# top_schema.net
KiCad netlist of a schematic drawn in Altium Designer
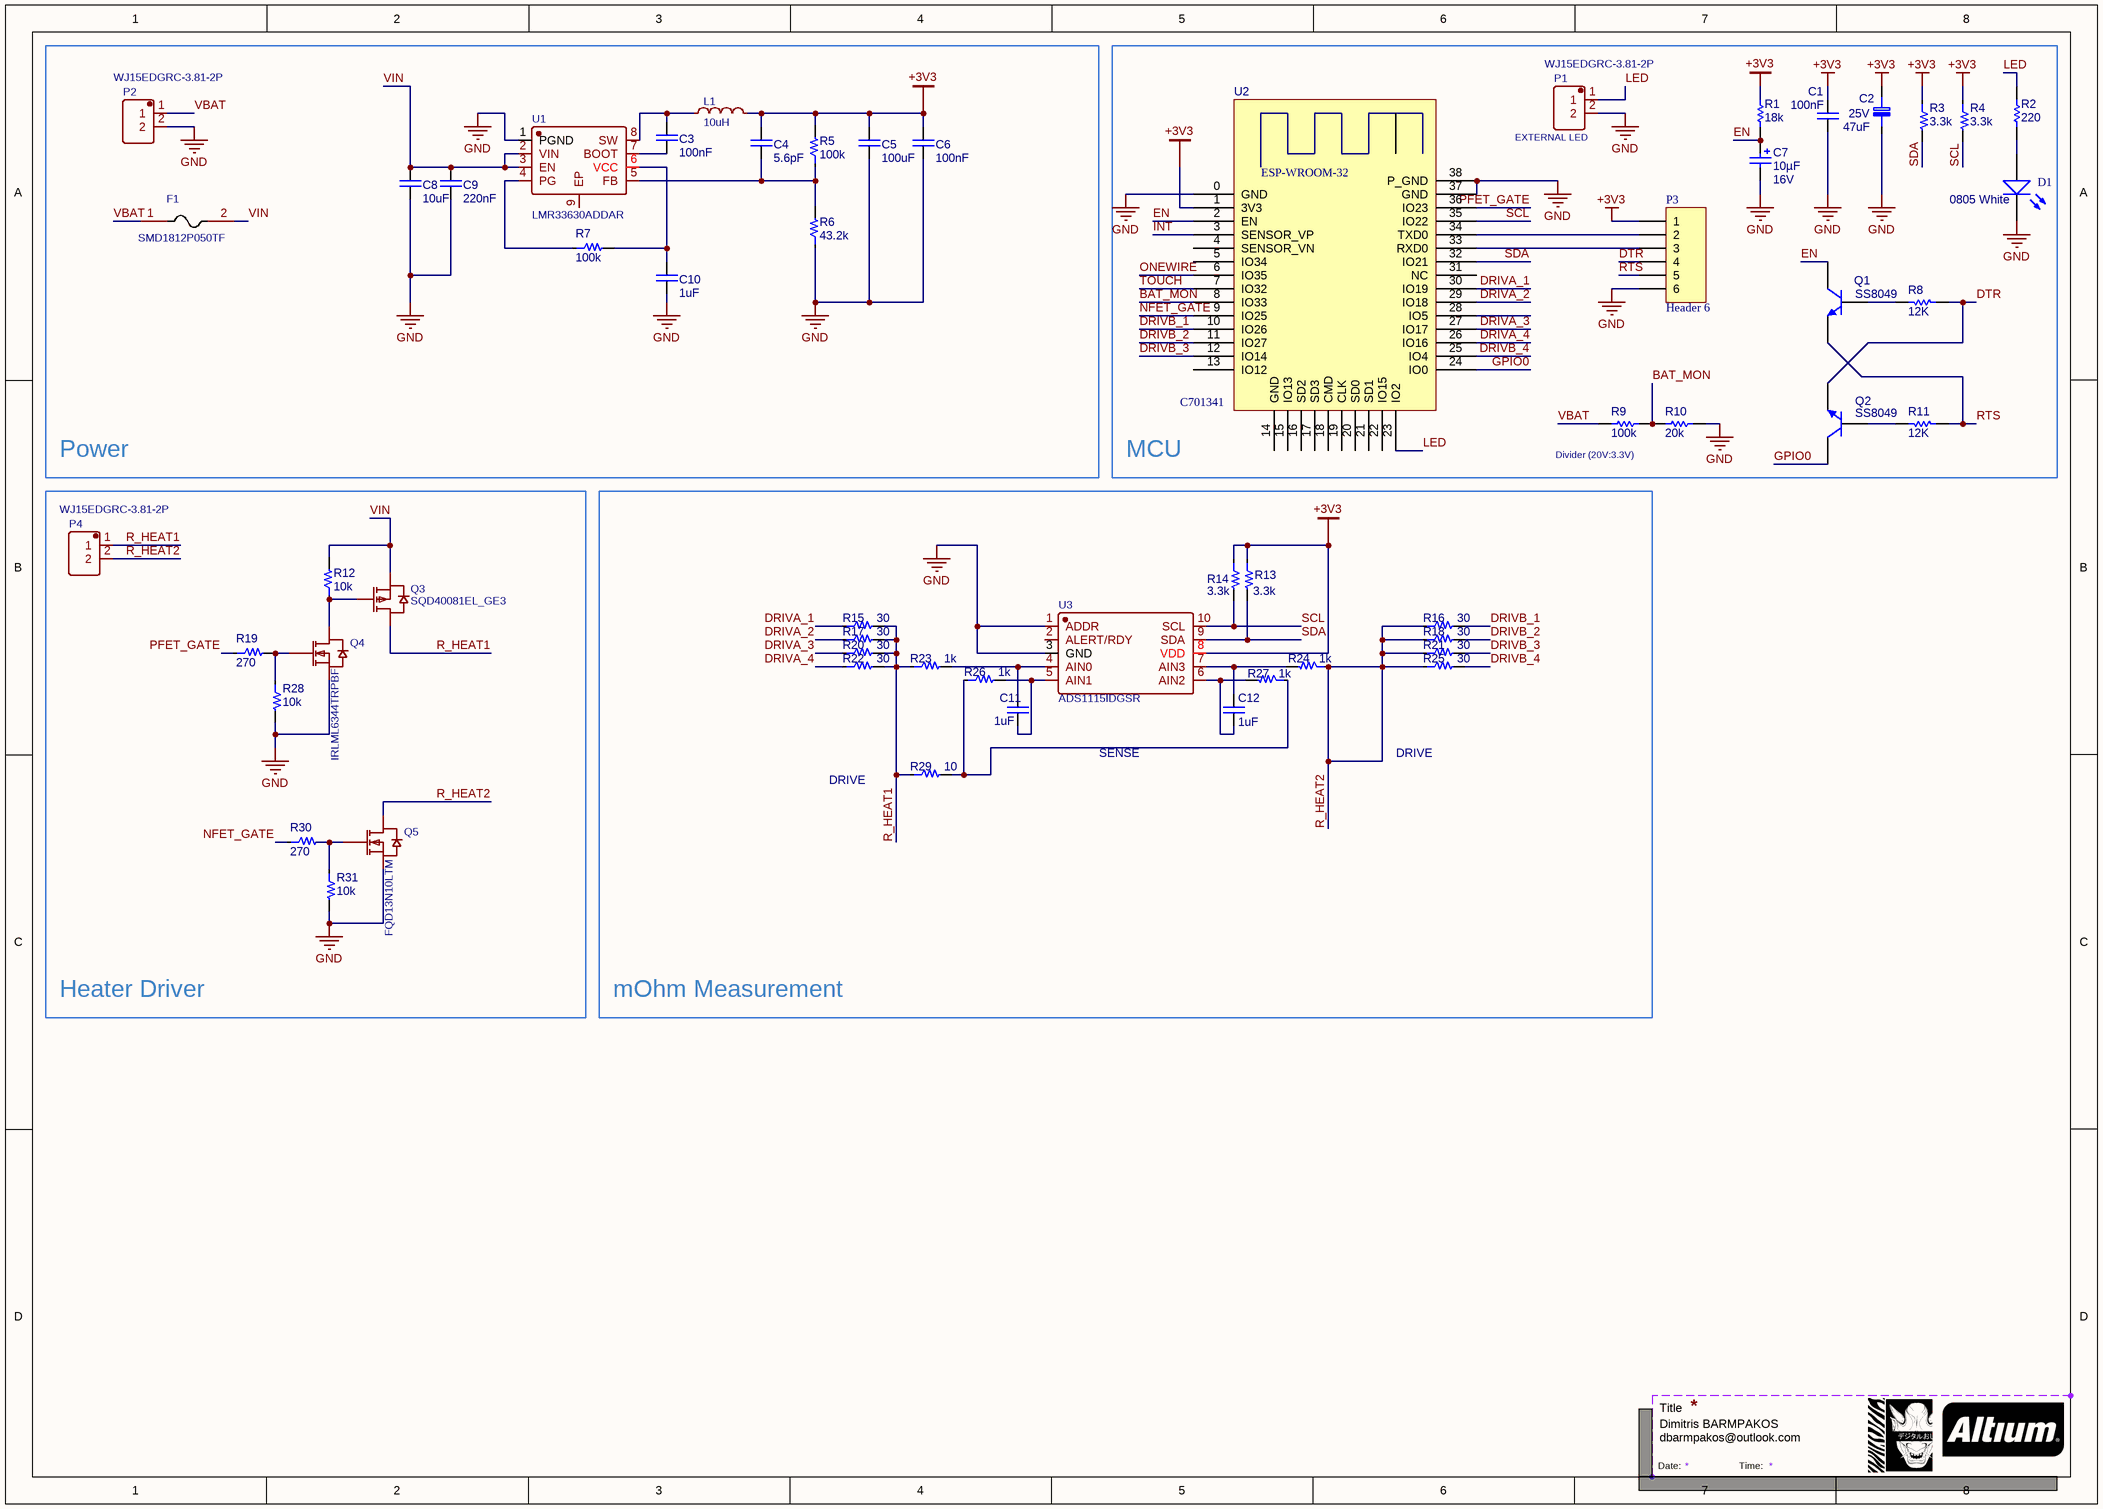
[diagram p0: top_schema.SchDoc]

(export (version "E")
  (design (tool "Eeschema 10.0.6"))
  (components
    (comp (ref "C1")
      (value "100nF")
      (footprint "CAP_0603")
      (description "CAP CER 0.1UF 50V X7R 0603")
      (fields
        (field (name "MANUFACTURER") "FH(Guangdong Fenghua Advanced Tech)")
        (field (name "MANUFACTURER PART NUMBER") "0603F104M500NT")
      )
      (libsource (lib "Schlib1") (part "CAP - CER 0.1UF 25V X7R 0805"))
    )
    (comp (ref "C2")
      (value "47uF")
      (footprint "CAP SMD 6.3X7.7")
      (description "CAP ALUM 22UF 20% 25V SMD")
      (fields
        (field (name "MANUFACTURER") "Nichicon")
        (field (name "MANUFACTURER PART NUMBER") "UWX1E220MCL1GB")
        (field (name "CAPACITANCE") "47uF")
        (field (name "VOLTAGE RATING") "25V")
      )
      (libsource (lib "Schlib1") (part "CAP 22UF 63V SMD"))
    )
    (comp (ref "C3")
      (value "100nF")
      (footprint "CAP_0603")
      (description "CAP CER 0.1UF 50V X7R 0603")
      (fields
        (field (name "MANUFACTURER") "FH(Guangdong Fenghua Advanced Tech)")
        (field (name "MANUFACTURER PART NUMBER") "0603F104M500NT")
      )
      (libsource (lib "thermoskin_v1") (part "CAP - CER 0.1UF 25V X7R 0805"))
    )
    (comp (ref "C4")
      (value "5.6pF")
      (footprint "CAP_0603")
      (description "CAP CER 0.1UF 50V X7R 0603")
      (fields
        (field (name "MANUFACTURER") "FH(Guangdong Fenghua Advanced Tech)")
        (field (name "MANUFACTURER PART NUMBER") "0603F104M500NT")
      )
      (libsource (lib "thermoskin_v1") (part "CAP - CER 0.1UF 25V X7R 0805"))
    )
    (comp (ref "C5")
      (value "100uF")
      (footprint "CAP_0603")
      (description "CAP CER 0.1UF 50V X7R 0603")
      (fields
        (field (name "MANUFACTURER") "FH(Guangdong Fenghua Advanced Tech)")
        (field (name "MANUFACTURER PART NUMBER") "0603F104M500NT")
      )
      (libsource (lib "thermoskin_v1") (part "CAP - CER 0.1UF 25V X7R 0805"))
    )
    (comp (ref "C6")
      (value "100nF")
      (footprint "CAP_0603")
      (description "CAP CER 0.1UF 50V X7R 0603")
      (fields
        (field (name "MANUFACTURER") "FH(Guangdong Fenghua Advanced Tech)")
        (field (name "MANUFACTURER PART NUMBER") "0603F104M500NT")
      )
      (libsource (lib "thermoskin_v1") (part "CAP - CER 0.1UF 25V X7R 0805"))
    )
    (comp (ref "C7")
      (value "10uF")
      (footprint "CAP_CERAM")
      (description "Tantalum Capacitor")
      (fields
        (field (name "MANUFACTURER") "Kemet")
        (field (name "MANUFACTURER PART NUMBER") "T491A106K016AT")
        (field (name "CAPACITANCE") "10µF")
        (field (name "VOLTAGE - RATED") "16V")
      )
      (libsource (lib "Schlib1") (part "Capacitor Polarized"))
    )
    (comp (ref "C8")
      (value "10uF")
      (footprint "CAP_0603")
      (description "CAP CER 0.1UF 50V X7R 0603")
      (fields
        (field (name "MANUFACTURER") "FH(Guangdong Fenghua Advanced Tech)")
        (field (name "MANUFACTURER PART NUMBER") "0603F104M500NT")
      )
      (libsource (lib "thermoskin_v1") (part "CAP - CER 0.1UF 25V X7R 0805"))
    )
    (comp (ref "C9")
      (value "220nF")
      (footprint "CAP_0603")
      (description "CAP CER 0.1UF 50V X7R 0603")
      (fields
        (field (name "MANUFACTURER") "FH(Guangdong Fenghua Advanced Tech)")
        (field (name "MANUFACTURER PART NUMBER") "0603F104M500NT")
      )
      (libsource (lib "thermoskin_v1") (part "CAP - CER 0.1UF 25V X7R 0805"))
    )
    (comp (ref "C10")
      (value "1uF")
      (footprint "CAP_0603")
      (description "CAP CER 0.1UF 50V X7R 0603")
      (fields
        (field (name "MANUFACTURER") "FH(Guangdong Fenghua Advanced Tech)")
        (field (name "MANUFACTURER PART NUMBER") "0603F104M500NT")
      )
      (libsource (lib "thermoskin_v1") (part "CAP - CER 0.1UF 25V X7R 0805"))
    )
    (comp (ref "C11")
      (value "1uF")
      (footprint "CAP_0603")
      (description "CAP CER 0.1UF 50V X7R 0603")
      (fields
        (field (name "MANUFACTURER") "FH(Guangdong Fenghua Advanced Tech)")
        (field (name "MANUFACTURER PART NUMBER") "0603F104M500NT")
      )
      (libsource (lib "Schlib1") (part "CAP - CER 0.1UF 25V X7R 0805"))
    )
    (comp (ref "C12")
      (value "1uF")
      (footprint "CAP_0603")
      (description "CAP CER 0.1UF 50V X7R 0603")
      (fields
        (field (name "MANUFACTURER") "FH(Guangdong Fenghua Advanced Tech)")
        (field (name "MANUFACTURER PART NUMBER") "0603F104M500NT")
      )
      (libsource (lib "Schlib1") (part "CAP - CER 0.1UF 25V X7R 0805"))
    )
    (comp (ref "D1")
      (value "0805 White")
      (footprint "0805_LED_S1")
      (description "LED")
      (libsource (lib "Miscellaneous Devices LC") (part "0805 LED White"))
    )
    (comp (ref "F1")
      (value "SMD1812P050TF")
      (footprint "SMT_FUSE")
      (description "C12559")
      (fields (field (name "BOM_SUPPLIER PART") "C12558"))
      (libsource (lib "Schlib1") (part "SMD1812P050TF"))
    )
    (comp (ref "L1")
      (value "10uH")
      (footprint "IND-SMD_L5.0-W5.0")
      (fields
        (field (name "BOM_MANUFACTURER PART") "SWPA5040S100MT")
        (field (name "BOM_SUPPLIER PART") "C84608")
      )
      (libsource (lib "thermoskin_v1") (part "10uH"))
    )
    (comp (ref "P1")
      (value "WJ15EDGRC-3.81-2P")
      (footprint "CONN-TH_2P-P3.81_WJ15EDGRC-3.81-2P")
      (description "C8387")
      (libsource (lib "Schlib1") (part "WJ15EDGRC-3.81-2P"))
    )
    (comp (ref "P2")
      (value "WJ15EDGRC-3.81-2P")
      (footprint "CONN-TH_2P-P3.81_WJ15EDGRC-3.81-2P")
      (description "C8387")
      (libsource (lib "Schlib1") (part "WJ15EDGRC-3.81-2P"))
    )
    (comp (ref "P3")
      (value "Header 6")
      (footprint "HDR1X6")
      (description "Header, 6-Pin")
      (fields (field (name "PUBLISHER") "Altium Limited"))
      (libsource (lib "Schlib1") (part "Header 6"))
    )
    (comp (ref "P4")
      (value "WJ15EDGRC-3.81-2P")
      (footprint "CONN-TH_2P-P3.81_WJ15EDGRC-3.81-2P")
      (description "C8387")
      (libsource (lib "Schlib1") (part "WJ15EDGRC-3.81-2P"))
    )
    (comp (ref "Q1")
      (value "SS8049")
      (footprint "SOT23")
      (description "NPN Bipolar Transistor")
      (fields (field (name "PUBLISHER") "Altium Limited"))
      (libsource (lib "Schlib1") (part "NPN"))
    )
    (comp (ref "Q2")
      (value "SS8049")
      (footprint "SOT23")
      (description "NPN Bipolar Transistor")
      (fields (field (name "PUBLISHER") "Altium Limited"))
      (libsource (lib "Schlib1") (part "NPN"))
    )
    (comp (ref "Q3")
      (value "SQD40081EL_GE3")
      (footprint "TO-252-3_L6.6-W6.1-P4.57-LS9.9-BR")
      (fields (field (name "BOM_SUPPLIER PART") "C727779") (field (name "CONTRIBUTOR") "LCSC"))
      (libsource (lib "thermoskin_v1") (part "SQD40081EL_GE3"))
    )
    (comp (ref "Q4")
      (value "IRLML6344TRPBF")
      (footprint "SOT-23-3_L2.9-W1.6-P1.90-LS2.8-BR")
      (fields (field (name "BOM_SUPPLIER PART") "C53550") (field (name "CONTRIBUTOR") "LCSC"))
      (libsource (lib "thermoskin_v1") (part "IRLML6344TRPBF"))
    )
    (comp (ref "Q5")
      (value "FQD13N10LTM")
      (footprint "TO-252-2_L6.6-W6.1-P4.57-LS9.9-TL-CW")
      (fields (field (name "BOM_SUPPLIER PART") "C37552"))
      (libsource (lib "Schlib1") (part "FQD13N10LTM"))
    )
    (comp (ref "R1")
      (value "18k")
      (footprint "R0603")
      (description "Res Thick Film 0603 1M Ohm 1% 0.1W(1/10W) ±100ppm/C Pad SMD T/R")
      (fields
        (field (name "MANUFACTURER") "TE Connectivity")
        (field (name "MANUFACTURER PART NUMBER") "CRG0603F1M0")
        (field (name "RESISTANCE") "18k")
      )
      (libsource (lib "Miscellaneous Devices") (part "Res1"))
    )
    (comp (ref "R2")
      (value "220")
      (footprint "R0603")
      (description "Res Thick Film 0603 1M Ohm 1% 0.1W(1/10W) ±100ppm/C Pad SMD T/R")
      (fields
        (field (name "MANUFACTURER") "TE Connectivity")
        (field (name "MANUFACTURER PART NUMBER") "CRG0603F1M0")
        (field (name "RESISTANCE") "220")
      )
      (libsource (lib "Miscellaneous Devices") (part "Res1"))
    )
    (comp (ref "R3")
      (value "3.3k")
      (footprint "R0603")
      (fields
        (field (name "MANUFACTURER") "UNI-ROYAL(Uniroyal Elec)")
        (field (name "MANUFACTURER PART NUMBER") "0603WAJ0472T5E")
        (field (name "RESISTANCE") "3.3k")
      )
      (libsource (lib "MIST_CKT_NEW") (part "Res 1k ±1% 0.063W 0402"))
    )
    (comp (ref "R4")
      (value "3.3k")
      (footprint "R0603")
      (fields
        (field (name "MANUFACTURER") "UNI-ROYAL(Uniroyal Elec)")
        (field (name "MANUFACTURER PART NUMBER") "0603WAJ0472T5E")
        (field (name "RESISTANCE") "3.3k")
      )
      (libsource (lib "MIST_CKT_NEW") (part "Res 1k ±1% 0.063W 0402"))
    )
    (comp (ref "R5")
      (value "100k")
      (footprint "R0603")
      (fields
        (field (name "MANUFACTURER") "UNI-ROYAL(Uniroyal Elec)")
        (field (name "MANUFACTURER PART NUMBER") "0603WAJ0472T5E")
        (field (name "RESISTANCE") "100k")
      )
      (libsource (lib "MIST_CKT_NEW") (part "Res 1k ±1% 0.063W 0402"))
    )
    (comp (ref "R6")
      (value "43.2k")
      (footprint "R0603")
      (fields
        (field (name "MANUFACTURER") "UNI-ROYAL(Uniroyal Elec)")
        (field (name "MANUFACTURER PART NUMBER") "0603WAJ0472T5E")
        (field (name "RESISTANCE") "43.2k")
      )
      (libsource (lib "MIST_CKT_NEW") (part "Res 1k ±1% 0.063W 0402"))
    )
    (comp (ref "R7")
      (value "100k")
      (footprint "R0603")
      (fields
        (field (name "MANUFACTURER") "UNI-ROYAL(Uniroyal Elec)")
        (field (name "MANUFACTURER PART NUMBER") "0603WAJ0472T5E")
        (field (name "RESISTANCE") "100k")
      )
      (libsource (lib "MIST_CKT_NEW") (part "Res 1k ±1% 0.063W 0402"))
    )
    (comp (ref "R8")
      (value "12k")
      (footprint "R0603")
      (description "Res Thkflm Anti-sulfurated 0603 100K Ohm 5% SMD")
      (fields
        (field (name "MANUFACTURER") "Panasonic")
        (field (name "MANUFACTURER PART NUMBER") "ERJ-U03J104V")
        (field (name "RESISTANCE") "12K")
      )
      (libsource (lib "Altium_Library") (part "Res1"))
    )
    (comp (ref "R9")
      (value "100k")
      (footprint "R0603")
      (description "Res Thick Film 0603 1M Ohm 1% 0.1W(1/10W) ±100ppm/C Pad SMD T/R")
      (fields
        (field (name "MANUFACTURER") "TE Connectivity")
        (field (name "MANUFACTURER PART NUMBER") "CRG0603F1M0")
        (field (name "RESISTANCE") "100k")
      )
      (libsource (lib "Miscellaneous Devices") (part "Res1"))
    )
    (comp (ref "R10")
      (value "20k")
      (footprint "R0603")
      (description "Res Thick Film 0603 1M Ohm 1% 0.1W(1/10W) ±100ppm/C Pad SMD T/R")
      (fields
        (field (name "MANUFACTURER") "TE Connectivity")
        (field (name "MANUFACTURER PART NUMBER") "CRG0603F1M0")
        (field (name "RESISTANCE") "20k")
      )
      (libsource (lib "Miscellaneous Devices") (part "Res1"))
    )
    (comp (ref "R11")
      (value "12k")
      (footprint "R0603")
      (description "Res Thkflm Anti-sulfurated 0603 100K Ohm 5% SMD")
      (fields
        (field (name "MANUFACTURER") "Panasonic")
        (field (name "MANUFACTURER PART NUMBER") "ERJ-U03J104V")
        (field (name "RESISTANCE") "12K")
      )
      (libsource (lib "Altium_Library") (part "Res1"))
    )
    (comp (ref "R12")
      (value "10k")
      (footprint "R0603")
      (fields
        (field (name "MANUFACTURER") "UNI-ROYAL(Uniroyal Elec)")
        (field (name "MANUFACTURER PART NUMBER") "0603WAJ0472T5E")
        (field (name "RESISTANCE") "10k")
      )
      (libsource (lib "MIST_CKT_NEW") (part "Res 1k ±1% 0.063W 0402"))
    )
    (comp (ref "R13")
      (value "3.3k")
      (footprint "R0603")
      (fields
        (field (name "MANUFACTURER") "UNI-ROYAL(Uniroyal Elec)")
        (field (name "MANUFACTURER PART NUMBER") "0603WAJ0472T5E")
        (field (name "RESISTANCE") "3.3k")
      )
      (libsource (lib "MIST_CKT_NEW") (part "Res 1k ±1% 0.063W 0402"))
    )
    (comp (ref "R14")
      (value "3.3k")
      (footprint "R0603")
      (fields
        (field (name "MANUFACTURER") "UNI-ROYAL(Uniroyal Elec)")
        (field (name "MANUFACTURER PART NUMBER") "0603WAJ0472T5E")
        (field (name "RESISTANCE") "3.3k")
      )
      (libsource (lib "MIST_CKT_NEW") (part "Res 1k ±1% 0.063W 0402"))
    )
    (comp (ref "R15")
      (value "30")
      (footprint "R0603")
      (fields
        (field (name "MANUFACTURER") "UNI-ROYAL(Uniroyal Elec)")
        (field (name "MANUFACTURER PART NUMBER") "0603WAJ0472T5E")
        (field (name "RESISTANCE") "30")
      )
      (libsource (lib "MIST_CKT_NEW") (part "Res 1k ±1% 0.063W 0402"))
    )
    (comp (ref "R16")
      (value "30")
      (footprint "R0603")
      (fields
        (field (name "MANUFACTURER") "UNI-ROYAL(Uniroyal Elec)")
        (field (name "MANUFACTURER PART NUMBER") "0603WAJ0472T5E")
        (field (name "RESISTANCE") "30")
      )
      (libsource (lib "MIST_CKT_NEW") (part "Res 1k ±1% 0.063W 0402"))
    )
    (comp (ref "R17")
      (value "30")
      (footprint "R0603")
      (fields
        (field (name "MANUFACTURER") "UNI-ROYAL(Uniroyal Elec)")
        (field (name "MANUFACTURER PART NUMBER") "0603WAJ0472T5E")
        (field (name "RESISTANCE") "30")
      )
      (libsource (lib "MIST_CKT_NEW") (part "Res 1k ±1% 0.063W 0402"))
    )
    (comp (ref "R18")
      (value "30")
      (footprint "R0603")
      (fields
        (field (name "MANUFACTURER") "UNI-ROYAL(Uniroyal Elec)")
        (field (name "MANUFACTURER PART NUMBER") "0603WAJ0472T5E")
        (field (name "RESISTANCE") "30")
      )
      (libsource (lib "MIST_CKT_NEW") (part "Res 1k ±1% 0.063W 0402"))
    )
    (comp (ref "R19")
      (value "270")
      (footprint "R0603")
      (fields
        (field (name "MANUFACTURER") "UNI-ROYAL(Uniroyal Elec)")
        (field (name "MANUFACTURER PART NUMBER") "0603WAJ0472T5E")
        (field (name "RESISTANCE") "270")
      )
      (libsource (lib "MIST_CKT_NEW") (part "Res 1k ±1% 0.063W 0402"))
    )
    (comp (ref "R20")
      (value "30")
      (footprint "R0603")
      (fields
        (field (name "MANUFACTURER") "UNI-ROYAL(Uniroyal Elec)")
        (field (name "MANUFACTURER PART NUMBER") "0603WAJ0472T5E")
        (field (name "RESISTANCE") "30")
      )
      (libsource (lib "MIST_CKT_NEW") (part "Res 1k ±1% 0.063W 0402"))
    )
    (comp (ref "R21")
      (value "30")
      (footprint "R0603")
      (fields
        (field (name "MANUFACTURER") "UNI-ROYAL(Uniroyal Elec)")
        (field (name "MANUFACTURER PART NUMBER") "0603WAJ0472T5E")
        (field (name "RESISTANCE") "30")
      )
      (libsource (lib "MIST_CKT_NEW") (part "Res 1k ±1% 0.063W 0402"))
    )
    (comp (ref "R22")
      (value "30")
      (footprint "R0603")
      (fields
        (field (name "MANUFACTURER") "UNI-ROYAL(Uniroyal Elec)")
        (field (name "MANUFACTURER PART NUMBER") "0603WAJ0472T5E")
        (field (name "RESISTANCE") "30")
      )
      (libsource (lib "MIST_CKT_NEW") (part "Res 1k ±1% 0.063W 0402"))
    )
    (comp (ref "R23")
      (value "1k")
      (footprint "R0603")
      (fields
        (field (name "MANUFACTURER") "UNI-ROYAL(Uniroyal Elec)")
        (field (name "MANUFACTURER PART NUMBER") "0603WAJ0472T5E")
        (field (name "RESISTANCE") "1k")
      )
      (libsource (lib "MIST_CKT_NEW") (part "Res 1k ±1% 0.063W 0402"))
    )
    (comp (ref "R24")
      (value "1k")
      (footprint "R0603")
      (fields
        (field (name "MANUFACTURER") "UNI-ROYAL(Uniroyal Elec)")
        (field (name "MANUFACTURER PART NUMBER") "0603WAJ0472T5E")
        (field (name "RESISTANCE") "1k")
      )
      (libsource (lib "MIST_CKT_NEW") (part "Res 1k ±1% 0.063W 0402"))
    )
    (comp (ref "R25")
      (value "30")
      (footprint "R0603")
      (fields
        (field (name "MANUFACTURER") "UNI-ROYAL(Uniroyal Elec)")
        (field (name "MANUFACTURER PART NUMBER") "0603WAJ0472T5E")
        (field (name "RESISTANCE") "30")
      )
      (libsource (lib "MIST_CKT_NEW") (part "Res 1k ±1% 0.063W 0402"))
    )
    (comp (ref "R26")
      (value "1k")
      (footprint "R0603")
      (fields
        (field (name "MANUFACTURER") "UNI-ROYAL(Uniroyal Elec)")
        (field (name "MANUFACTURER PART NUMBER") "0603WAJ0472T5E")
        (field (name "RESISTANCE") "1k")
      )
      (libsource (lib "MIST_CKT_NEW") (part "Res 1k ±1% 0.063W 0402"))
    )
    (comp (ref "R27")
      (value "1k")
      (footprint "R0603")
      (fields
        (field (name "MANUFACTURER") "UNI-ROYAL(Uniroyal Elec)")
        (field (name "MANUFACTURER PART NUMBER") "0603WAJ0472T5E")
        (field (name "RESISTANCE") "1k")
      )
      (libsource (lib "MIST_CKT_NEW") (part "Res 1k ±1% 0.063W 0402"))
    )
    (comp (ref "R28")
      (value "10k")
      (footprint "R0603")
      (fields
        (field (name "MANUFACTURER") "UNI-ROYAL(Uniroyal Elec)")
        (field (name "MANUFACTURER PART NUMBER") "0603WAJ0472T5E")
        (field (name "RESISTANCE") "10k")
      )
      (libsource (lib "MIST_CKT_NEW") (part "Res 1k ±1% 0.063W 0402"))
    )
    (comp (ref "R29")
      (value "10")
      (footprint "R0603")
      (fields
        (field (name "MANUFACTURER") "UNI-ROYAL(Uniroyal Elec)")
        (field (name "MANUFACTURER PART NUMBER") "0603WAJ0472T5E")
        (field (name "RESISTANCE") "10")
      )
      (libsource (lib "MIST_CKT_NEW") (part "Res 1k ±1% 0.063W 0402"))
    )
    (comp (ref "R30")
      (value "270")
      (footprint "R0603")
      (fields
        (field (name "MANUFACTURER") "UNI-ROYAL(Uniroyal Elec)")
        (field (name "MANUFACTURER PART NUMBER") "0603WAJ0472T5E")
        (field (name "RESISTANCE") "270")
      )
      (libsource (lib "MIST_CKT_NEW") (part "Res 1k ±1% 0.063W 0402"))
    )
    (comp (ref "R31")
      (value "10k")
      (footprint "R0603")
      (fields
        (field (name "MANUFACTURER") "UNI-ROYAL(Uniroyal Elec)")
        (field (name "MANUFACTURER PART NUMBER") "0603WAJ0472T5E")
        (field (name "RESISTANCE") "10k")
      )
      (libsource (lib "MIST_CKT_NEW") (part "Res 1k ±1% 0.063W 0402"))
    )
    (comp (ref "U1")
      (value "LMR33630ADDAR")
      (footprint "ESOP-8_L4.9-W3.9-P1.27-LS6.0-TL-EP")
      (fields (field (name "BOM_SUPPLIER PART") "C841384") (field (name "CONTRIBUTOR") "LCSC"))
      (libsource (lib "thermoskin_v1") (part "LMR33630ADDAR_1"))
    )
    (comp (ref "U2") (value "C701341") (footprint "ESP32_WROOM") (libsource (lib "Schlib1") (part "ESP 32")))
    (comp (ref "U3")
      (value "ADS1115IDGSR")
      (footprint "MSOP-10_L3.0-W3.0-P0.50-LS5.0-BL")
      (description "C37593")
      (libsource (lib "Schlib1") (part "ADS1115IDGSR"))
    )
  )
  (nets
    (net (code "1") (name "+3V3") (class "Default")
      (node (ref "C1") (pin "1") (pinfunction "1_1") (pintype "passive"))
      (node (ref "C2") (pin "1") (pinfunction "1_1") (pintype "passive"))
      (node (ref "C4") (pin "1") (pinfunction "1_1") (pintype "passive"))
      (node (ref "C5") (pin "1") (pinfunction "1_1") (pintype "passive"))
      (node (ref "C6") (pin "1") (pinfunction "1_1") (pintype "passive"))
      (node (ref "L1") (pin "2") (pinfunction "2_2") (pintype "passive"))
      (node (ref "P3") (pin "1") (pinfunction "1_1") (pintype "passive"))
      (node (ref "R1") (pin "1") (pinfunction "1_1") (pintype "passive"))
      (node (ref "R13") (pin "1") (pinfunction "1_1") (pintype "passive"))
      (node (ref "R14") (pin "1") (pinfunction "1_1") (pintype "passive"))
      (node (ref "R3") (pin "1") (pinfunction "1_1") (pintype "passive"))
      (node (ref "R4") (pin "1") (pinfunction "1_1") (pintype "passive"))
      (node (ref "R5") (pin "2") (pinfunction "2_2") (pintype "passive"))
      (node (ref "U2") (pin "1") (pinfunction "3V3_1") (pintype "passive"))
      (node (ref "U3") (pin "8") (pinfunction "VDD_8") (pintype "passive"))
    )
    (net (code "2") (name "/BAT_MON") (class "Default")
      (node (ref "R10") (pin "1") (pinfunction "1_1") (pintype "passive"))
      (node (ref "R9") (pin "2") (pinfunction "2_2") (pintype "passive"))
      (node (ref "U2") (pin "8") (pinfunction "IO33_8") (pintype "passive"))
    )
    (net (code "3") (name "/DRIVA_1") (class "Default")
      (node (ref "R15") (pin "1") (pinfunction "1_1") (pintype "passive"))
      (node (ref "U2") (pin "30") (pinfunction "IO19_30") (pintype "passive"))
    )
    (net (code "4") (name "/DRIVA_2") (class "Default")
      (node (ref "R17") (pin "1") (pinfunction "1_1") (pintype "passive"))
      (node (ref "U2") (pin "29") (pinfunction "IO18_29") (pintype "passive"))
    )
    (net (code "5") (name "/DRIVA_3") (class "Default")
      (node (ref "R20") (pin "1") (pinfunction "1_1") (pintype "passive"))
      (node (ref "U2") (pin "27") (pinfunction "IO17_27") (pintype "passive"))
    )
    (net (code "6") (name "/DRIVA_4") (class "Default")
      (node (ref "R22") (pin "1") (pinfunction "1_1") (pintype "passive"))
      (node (ref "U2") (pin "26") (pinfunction "IO16_26") (pintype "passive"))
    )
    (net (code "7") (name "/DRIVB_1") (class "Default")
      (node (ref "R16") (pin "2") (pinfunction "2_2") (pintype "passive"))
      (node (ref "U2") (pin "10") (pinfunction "IO26_10") (pintype "passive"))
    )
    (net (code "8") (name "/DRIVB_2") (class "Default")
      (node (ref "R18") (pin "2") (pinfunction "2_2") (pintype "passive"))
      (node (ref "U2") (pin "11") (pinfunction "IO27_11") (pintype "passive"))
    )
    (net (code "9") (name "/DRIVB_3") (class "Default")
      (node (ref "R21") (pin "2") (pinfunction "2_2") (pintype "passive"))
      (node (ref "U2") (pin "12") (pinfunction "IO14_12") (pintype "passive"))
    )
    (net (code "10") (name "/DRIVB_4") (class "Default")
      (node (ref "R25") (pin "2") (pinfunction "2_2") (pintype "passive"))
      (node (ref "U2") (pin "25") (pinfunction "IO4_25") (pintype "passive"))
    )
    (net (code "11") (name "/DTR") (class "Default")
      (node (ref "P3") (pin "4") (pinfunction "4_4") (pintype "passive"))
      (node (ref "Q2") (pin "2") (pinfunction "E_2") (pintype "passive"))
      (node (ref "R8") (pin "2") (pinfunction "2_2") (pintype "passive"))
    )
    (net (code "12") (name "/EN") (class "Default")
      (node (ref "C7") (pin "1") (pinfunction "1_1") (pintype "passive"))
      (node (ref "Q1") (pin "3") (pinfunction "C_3") (pintype "passive"))
      (node (ref "R1") (pin "2") (pinfunction "2_2") (pintype "passive"))
      (node (ref "U2") (pin "2") (pinfunction "EN_2") (pintype "passive"))
    )
    (net (code "13") (name "/GPIO0") (class "Default")
      (node (ref "Q2") (pin "3") (pinfunction "C_3") (pintype "passive"))
      (node (ref "U2") (pin "24") (pinfunction "IO0_24") (pintype "passive"))
    )
    (net (code "14") (name "/INT") (class "Default")
      (node (ref "U2") (pin "3") (pinfunction "SENSOR_VP_3") (pintype "passive"))
    )
    (net (code "15") (name "/LED") (class "Default")
      (node (ref "P1") (pin "1") (pinfunction "1_1") (pintype "passive"))
      (node (ref "R2") (pin "2") (pinfunction "2_2") (pintype "passive"))
      (node (ref "U2") (pin "23") (pinfunction "IO2_23") (pintype "passive"))
    )
    (net (code "16") (name "/NFET_GATE") (class "Default")
      (node (ref "R30") (pin "1") (pinfunction "1_1") (pintype "passive"))
      (node (ref "U2") (pin "9") (pinfunction "IO25_9") (pintype "passive"))
    )
    (net (code "17") (name "/ONEWIRE") (class "Default")
      (node (ref "U2") (pin "6") (pinfunction "IO35_6") (pintype "passive"))
    )
    (net (code "18") (name "/PFET_GATE") (class "Default")
      (node (ref "R19") (pin "1") (pinfunction "1_1") (pintype "passive"))
      (node (ref "U2") (pin "36") (pinfunction "IO23_36") (pintype "passive"))
    )
    (net (code "19") (name "/RTS") (class "Default")
      (node (ref "P3") (pin "5") (pinfunction "5_5") (pintype "passive"))
      (node (ref "Q1") (pin "2") (pinfunction "E_2") (pintype "passive"))
      (node (ref "R11") (pin "2") (pinfunction "2_2") (pintype "passive"))
    )
    (net (code "20") (name "/R_HEAT1") (class "Default")
      (node (ref "P4") (pin "1") (pinfunction "1_1") (pintype "passive"))
      (node (ref "Q3") (pin "3") (pinfunction "D_3") (pintype "passive"))
      (node (ref "R15") (pin "2") (pinfunction "2_2") (pintype "passive"))
      (node (ref "R17") (pin "2") (pinfunction "2_2") (pintype "passive"))
      (node (ref "R20") (pin "2") (pinfunction "2_2") (pintype "passive"))
      (node (ref "R22") (pin "2") (pinfunction "2_2") (pintype "passive"))
      (node (ref "R23") (pin "1") (pinfunction "1_1") (pintype "passive"))
      (node (ref "R29") (pin "1") (pinfunction "1_1") (pintype "passive"))
    )
    (net (code "21") (name "/R_HEAT2") (class "Default")
      (node (ref "P4") (pin "2") (pinfunction "2_2") (pintype "passive"))
      (node (ref "Q5") (pin "2") (pinfunction "D_2") (pintype "passive"))
      (node (ref "R16") (pin "1") (pinfunction "1_1") (pintype "passive"))
      (node (ref "R18") (pin "1") (pinfunction "1_1") (pintype "passive"))
      (node (ref "R21") (pin "1") (pinfunction "1_1") (pintype "passive"))
      (node (ref "R24") (pin "1") (pinfunction "1_1") (pintype "passive"))
      (node (ref "R25") (pin "1") (pinfunction "1_1") (pintype "passive"))
    )
    (net (code "22") (name "/SCL") (class "Default")
      (node (ref "R14") (pin "2") (pinfunction "2_2") (pintype "passive"))
      (node (ref "R4") (pin "2") (pinfunction "2_2") (pintype "passive"))
      (node (ref "U2") (pin "35") (pinfunction "IO22_35") (pintype "passive"))
      (node (ref "U3") (pin "10") (pinfunction "SCL_10") (pintype "passive"))
    )
    (net (code "23") (name "/SDA") (class "Default")
      (node (ref "R13") (pin "2") (pinfunction "2_2") (pintype "passive"))
      (node (ref "R3") (pin "2") (pinfunction "2_2") (pintype "passive"))
      (node (ref "U2") (pin "32") (pinfunction "IO21_32") (pintype "passive"))
      (node (ref "U3") (pin "9") (pinfunction "SDA_9") (pintype "passive"))
    )
    (net (code "24") (name "/TOUCH") (class "Default")
      (node (ref "U2") (pin "7") (pinfunction "IO32_7") (pintype "passive"))
    )
    (net (code "25") (name "/VBAT") (class "Default")
      (node (ref "F1") (pin "1") (pinfunction "1_1") (pintype "passive"))
      (node (ref "P2") (pin "1") (pinfunction "1_1") (pintype "passive"))
      (node (ref "R9") (pin "1") (pinfunction "1_1") (pintype "passive"))
    )
    (net (code "26") (name "/VIN") (class "Default")
      (node (ref "C8") (pin "1") (pinfunction "1_1") (pintype "passive"))
      (node (ref "C9") (pin "1") (pinfunction "1_1") (pintype "passive"))
      (node (ref "F1") (pin "2") (pinfunction "2_2") (pintype "passive"))
      (node (ref "Q3") (pin "2") (pinfunction "S_2") (pintype "passive"))
      (node (ref "R12") (pin "2") (pinfunction "2_2") (pintype "passive"))
      (node (ref "U1") (pin "2") (pinfunction "VIN_2") (pintype "passive"))
      (node (ref "U1") (pin "3") (pinfunction "EN_3") (pintype "passive"))
    )
    (net (code "27") (name "GND") (class "Default")
      (node (ref "C1") (pin "2") (pinfunction "2_2") (pintype "passive"))
      (node (ref "C10") (pin "2") (pinfunction "2_2") (pintype "passive"))
      (node (ref "C2") (pin "2") (pinfunction "2_2") (pintype "passive"))
      (node (ref "C5") (pin "2") (pinfunction "2_2") (pintype "passive"))
      (node (ref "C6") (pin "2") (pinfunction "2_2") (pintype "passive"))
      (node (ref "C7") (pin "2") (pinfunction "2_2") (pintype "passive"))
      (node (ref "C8") (pin "2") (pinfunction "2_2") (pintype "passive"))
      (node (ref "C9") (pin "2") (pinfunction "2_2") (pintype "passive"))
      (node (ref "D1") (pin "K") (pinfunction "K_K") (pintype "passive"))
      (node (ref "P1") (pin "2") (pinfunction "2_2") (pintype "passive"))
      (node (ref "P2") (pin "2") (pinfunction "2_2") (pintype "passive"))
      (node (ref "P3") (pin "6") (pinfunction "6_6") (pintype "passive"))
      (node (ref "Q4") (pin "2") (pinfunction "S_2") (pintype "passive"))
      (node (ref "Q5") (pin "3") (pinfunction "S_3") (pintype "passive"))
      (node (ref "R10") (pin "2") (pinfunction "2_2") (pintype "passive"))
      (node (ref "R28") (pin "2") (pinfunction "2_2") (pintype "passive"))
      (node (ref "R31") (pin "2") (pinfunction "2_2") (pintype "passive"))
      (node (ref "R6") (pin "1") (pinfunction "1_1") (pintype "passive"))
      (node (ref "U1") (pin "1") (pinfunction "PGND_1") (pintype "passive"))
      (node (ref "U2") (pin "0") (pinfunction "GND_0") (pintype "passive"))
      (node (ref "U2") (pin "37") (pinfunction "GND_37") (pintype "passive"))
      (node (ref "U2") (pin "38") (pinfunction "P_GND_38") (pintype "passive"))
      (node (ref "U3") (pin "1") (pinfunction "ADDR_1") (pintype "passive"))
      (node (ref "U3") (pin "3") (pinfunction "GND_3") (pintype "passive"))
    )
    (net (code "28") (name "Net-(D1-PadA)") (class "Default")
      (node (ref "D1") (pin "A") (pinfunction "A_A") (pintype "passive"))
      (node (ref "R2") (pin "1") (pinfunction "1_1") (pintype "passive"))
    )
    (net (code "29") (name "Net-(Q1-B)") (class "Default")
      (node (ref "Q1") (pin "1") (pinfunction "B_1") (pintype "passive"))
      (node (ref "R8") (pin "1") (pinfunction "1_1") (pintype "passive"))
    )
    (net (code "30") (name "Net-(Q2-B)") (class "Default")
      (node (ref "Q2") (pin "1") (pinfunction "B_1") (pintype "passive"))
      (node (ref "R11") (pin "1") (pinfunction "1_1") (pintype "passive"))
    )
    (net (code "31") (name "Net-(Q3-G)") (class "Default")
      (node (ref "Q3") (pin "1") (pinfunction "G_1") (pintype "passive"))
      (node (ref "Q4") (pin "3") (pinfunction "D_3") (pintype "passive"))
      (node (ref "R12") (pin "1") (pinfunction "1_1") (pintype "passive"))
    )
    (net (code "32") (name "Net-(Q4-G)") (class "Default")
      (node (ref "Q4") (pin "1") (pinfunction "G_1") (pintype "passive"))
      (node (ref "R19") (pin "2") (pinfunction "2_2") (pintype "passive"))
      (node (ref "R28") (pin "1") (pinfunction "1_1") (pintype "passive"))
    )
    (net (code "33") (name "Net-(Q5-G)") (class "Default")
      (node (ref "Q5") (pin "1") (pinfunction "G_1") (pintype "passive"))
      (node (ref "R30") (pin "2") (pinfunction "2_2") (pintype "passive"))
      (node (ref "R31") (pin "1") (pinfunction "1_1") (pintype "passive"))
    )
    (net (code "34") (name "Net-(R26-Pad1)") (class "Default")
      (node (ref "R26") (pin "1") (pinfunction "1_1") (pintype "passive"))
      (node (ref "R27") (pin "1") (pinfunction "1_1") (pintype "passive"))
      (node (ref "R29") (pin "2") (pinfunction "2_2") (pintype "passive"))
    )
    (net (code "35") (name "Net-(U1-BOOT)") (class "Default")
      (node (ref "C3") (pin "1") (pinfunction "1_1") (pintype "passive"))
      (node (ref "U1") (pin "7") (pinfunction "BOOT_7") (pintype "passive"))
    )
    (net (code "36") (name "Net-(U1-FB)") (class "Default")
      (node (ref "C4") (pin "2") (pinfunction "2_2") (pintype "passive"))
      (node (ref "R5") (pin "1") (pinfunction "1_1") (pintype "passive"))
      (node (ref "R6") (pin "2") (pinfunction "2_2") (pintype "passive"))
      (node (ref "U1") (pin "5") (pinfunction "FB_5") (pintype "passive"))
    )
    (net (code "37") (name "Net-(U1-PG)") (class "Default")
      (node (ref "R7") (pin "1") (pinfunction "1_1") (pintype "passive"))
      (node (ref "U1") (pin "4") (pinfunction "PG_4") (pintype "passive"))
    )
    (net (code "38") (name "Net-(U1-SW)") (class "Default")
      (node (ref "C3") (pin "2") (pinfunction "2_2") (pintype "passive"))
      (node (ref "L1") (pin "1") (pinfunction "1_1") (pintype "passive"))
      (node (ref "U1") (pin "8") (pinfunction "SW_8") (pintype "passive"))
    )
    (net (code "39") (name "Net-(U1-VCC)") (class "Default")
      (node (ref "C10") (pin "1") (pinfunction "1_1") (pintype "passive"))
      (node (ref "R7") (pin "2") (pinfunction "2_2") (pintype "passive"))
      (node (ref "U1") (pin "6") (pinfunction "VCC_6") (pintype "passive"))
    )
    (net (code "40") (name "Net-(U2-RXD0)") (class "Default")
      (node (ref "P3") (pin "3") (pinfunction "3_3") (pintype "passive"))
      (node (ref "U2") (pin "33") (pinfunction "RXD0_33") (pintype "passive"))
    )
    (net (code "41") (name "Net-(U2-TXD0)") (class "Default")
      (node (ref "P3") (pin "2") (pinfunction "2_2") (pintype "passive"))
      (node (ref "U2") (pin "34") (pinfunction "TXD0_34") (pintype "passive"))
    )
    (net (code "42") (name "Net-(U3-AIN0)") (class "Default")
      (node (ref "C11") (pin "1") (pinfunction "1_1") (pintype "passive"))
      (node (ref "R23") (pin "2") (pinfunction "2_2") (pintype "passive"))
      (node (ref "U3") (pin "4") (pinfunction "AIN0_4") (pintype "passive"))
    )
    (net (code "43") (name "Net-(U3-AIN1)") (class "Default")
      (node (ref "C11") (pin "2") (pinfunction "2_2") (pintype "passive"))
      (node (ref "R26") (pin "2") (pinfunction "2_2") (pintype "passive"))
      (node (ref "U3") (pin "5") (pinfunction "AIN1_5") (pintype "passive"))
    )
    (net (code "44") (name "Net-(U3-AIN2)") (class "Default")
      (node (ref "C12") (pin "2") (pinfunction "2_2") (pintype "passive"))
      (node (ref "R27") (pin "2") (pinfunction "2_2") (pintype "passive"))
      (node (ref "U3") (pin "6") (pinfunction "AIN2_6") (pintype "passive"))
    )
    (net (code "45") (name "Net-(U3-AIN3)") (class "Default")
      (node (ref "C12") (pin "1") (pinfunction "1_1") (pintype "passive"))
      (node (ref "R24") (pin "2") (pinfunction "2_2") (pintype "passive"))
      (node (ref "U3") (pin "7") (pinfunction "AIN3_7") (pintype "passive"))
    )
    (net (code "46") (name "unconnected-(U1-EP-Pad9)") (class "Default")
      (node (ref "U1") (pin "9") (pinfunction "EP_9") (pintype "passive"))
    )
    (net (code "47") (name "unconnected-(U2-CLK-Pad19)") (class "Default")
      (node (ref "U2") (pin "19") (pinfunction "CLK_19") (pintype "passive"))
    )
    (net (code "48") (name "unconnected-(U2-CMD-Pad18)") (class "Default")
      (node (ref "U2") (pin "18") (pinfunction "CMD_18") (pintype "passive"))
    )
    (net (code "49") (name "unconnected-(U2-GND-Pad14)") (class "Default")
      (node (ref "U2") (pin "14") (pinfunction "GND_14") (pintype "passive"))
    )
    (net (code "50") (name "unconnected-(U2-IO5-Pad28)") (class "Default")
      (node (ref "U2") (pin "28") (pinfunction "IO5_28") (pintype "passive"))
    )
    (net (code "51") (name "unconnected-(U2-IO12-Pad13)") (class "Default")
      (node (ref "U2") (pin "13") (pinfunction "IO12_13") (pintype "passive"))
    )
    (net (code "52") (name "unconnected-(U2-IO13-Pad15)") (class "Default")
      (node (ref "U2") (pin "15") (pinfunction "IO13_15") (pintype "passive"))
    )
    (net (code "53") (name "unconnected-(U2-IO15-Pad22)") (class "Default")
      (node (ref "U2") (pin "22") (pinfunction "IO15_22") (pintype "passive"))
    )
    (net (code "54") (name "unconnected-(U2-IO34-Pad5)") (class "Default")
      (node (ref "U2") (pin "5") (pinfunction "IO34_5") (pintype "passive"))
    )
    (net (code "55") (name "unconnected-(U2-NC-Pad31)") (class "Default")
      (node (ref "U2") (pin "31") (pinfunction "NC_31") (pintype "passive"))
    )
    (net (code "56") (name "unconnected-(U2-SD0-Pad20)") (class "Default")
      (node (ref "U2") (pin "20") (pinfunction "SD0_20") (pintype "passive"))
    )
    (net (code "57") (name "unconnected-(U2-SD1-Pad21)") (class "Default")
      (node (ref "U2") (pin "21") (pinfunction "SD1_21") (pintype "passive"))
    )
    (net (code "58") (name "unconnected-(U2-SD2-Pad16)") (class "Default")
      (node (ref "U2") (pin "16") (pinfunction "SD2_16") (pintype "passive"))
    )
    (net (code "59") (name "unconnected-(U2-SD3-Pad17)") (class "Default")
      (node (ref "U2") (pin "17") (pinfunction "SD3_17") (pintype "passive"))
    )
    (net (code "60") (name "unconnected-(U2-SENSOR_VN-Pad4)") (class "Default")
      (node (ref "U2") (pin "4") (pinfunction "SENSOR_VN_4") (pintype "passive"))
    )
    (net (code "61") (name "unconnected-(U3-ALERT{slash}RDY-Pad2)") (class "Default")
      (node (ref "U3") (pin "2") (pinfunction "ALERT/RDY_2") (pintype "passive"))
    )
  )
)
